# double-offset.net
KiCad netlist of a schematic drawn in EAGLE
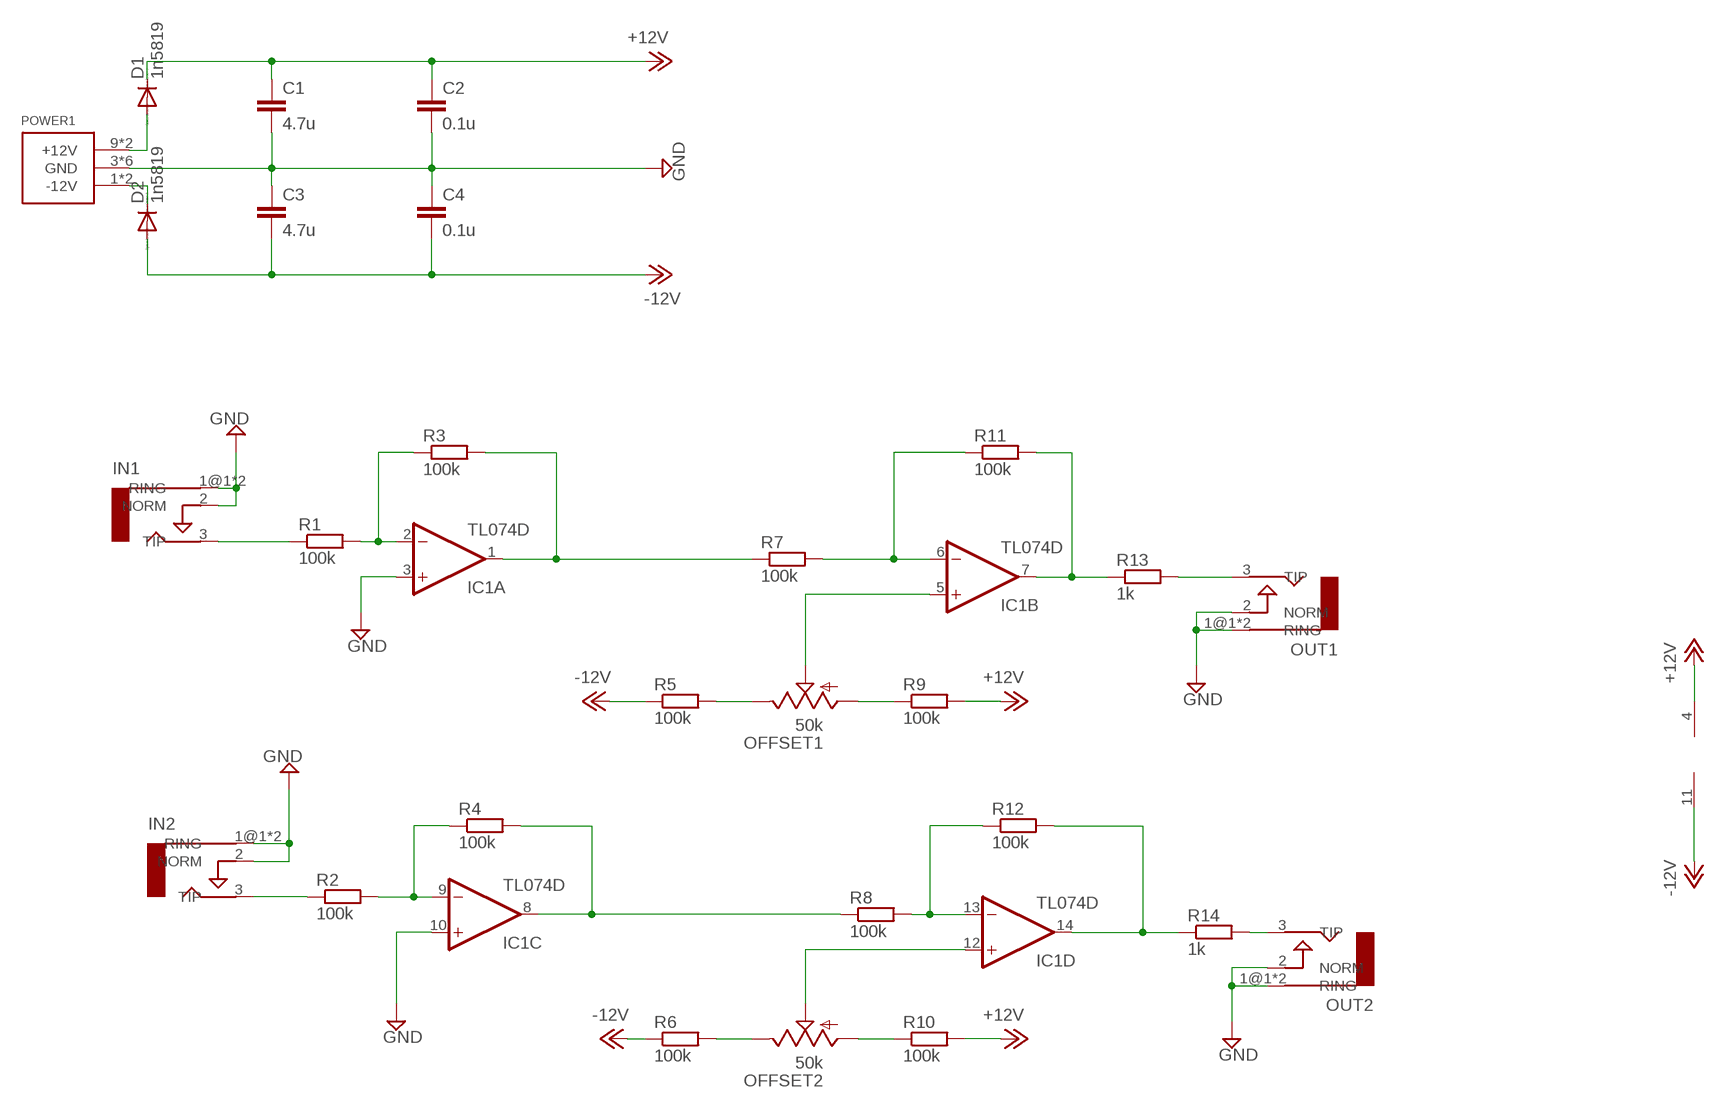
[diagram p0: schematic, sheet 1]

(export (version "E")
  (design (tool "Eeschema 10.0.6"))
  (components
    (comp (ref "C1")
      (value "4.7u")
      (footprint "eagle-import:C0805")
      (libsource (lib "eagle-import") (part "C-EUC0805"))
    )
    (comp (ref "C2")
      (value "0.1u")
      (footprint "eagle-import:C0805")
      (libsource (lib "eagle-import") (part "C-EUC0805"))
    )
    (comp (ref "C3")
      (value "4.7u")
      (footprint "eagle-import:C0805")
      (libsource (lib "eagle-import") (part "C-EUC0805"))
    )
    (comp (ref "C4")
      (value "0.1u")
      (footprint "eagle-import:C0805")
      (libsource (lib "eagle-import") (part "C-EUC0805"))
    )
    (comp (ref "D1")
      (value "1n5819")
      (footprint "eagle-import:SOD323-W")
      (libsource (lib "eagle-import") (part "DIODE-SOD323-W"))
    )
    (comp (ref "D2")
      (value "1n5819")
      (footprint "eagle-import:SOD323-W")
      (libsource (lib "eagle-import") (part "DIODE-SOD323-W"))
    )
    (comp (ref "IC1")
      (value "TL074D")
      (footprint "eagle-import:SO14")
      (libsource (lib "eagle-import") (part "TL074D"))
    )
    (comp (ref "IN1")
      (value "AUDIO-JACKERTHENVAR")
      (footprint "eagle-import:ERTHENVAR-JACK")
      (libsource (lib "eagle-import") (part "AUDIO-JACKERTHENVAR"))
    )
    (comp (ref "IN2")
      (value "AUDIO-JACKERTHENVAR")
      (footprint "eagle-import:ERTHENVAR-JACK")
      (libsource (lib "eagle-import") (part "AUDIO-JACKERTHENVAR"))
    )
    (comp (ref "OFFSET1")
      (value "50k")
      (footprint "eagle-import:9MM_SNAP-IN_POT")
      (libsource (lib "eagle-import") (part "9MM_SNAP-IN_POT_"))
    )
    (comp (ref "OFFSET2")
      (value "50k")
      (footprint "eagle-import:9MM_SNAP-IN_POT")
      (libsource (lib "eagle-import") (part "9MM_SNAP-IN_POT_"))
    )
    (comp (ref "OUT1")
      (value "AUDIO-JACKERTHENVAR")
      (footprint "eagle-import:ERTHENVAR-JACK")
      (libsource (lib "eagle-import") (part "AUDIO-JACKERTHENVAR"))
    )
    (comp (ref "OUT2")
      (value "AUDIO-JACKERTHENVAR")
      (footprint "eagle-import:ERTHENVAR-JACK")
      (libsource (lib "eagle-import") (part "AUDIO-JACKERTHENVAR"))
    )
    (comp (ref "POWER1")
      (value "POWER_SIMPLE10")
      (footprint "eagle-import:POWER_10")
      (libsource (lib "eagle-import") (part "POWER_SIMPLE10"))
    )
    (comp (ref "R1")
      (value "100k")
      (footprint "eagle-import:R0805")
      (libsource (lib "eagle-import") (part "R-EU_R0805"))
    )
    (comp (ref "R2")
      (value "100k")
      (footprint "eagle-import:R0805")
      (libsource (lib "eagle-import") (part "R-EU_R0805"))
    )
    (comp (ref "R3")
      (value "100k")
      (footprint "eagle-import:R0805")
      (libsource (lib "eagle-import") (part "R-EU_R0805"))
    )
    (comp (ref "R4")
      (value "100k")
      (footprint "eagle-import:R0805")
      (libsource (lib "eagle-import") (part "R-EU_R0805"))
    )
    (comp (ref "R5")
      (value "100k")
      (footprint "eagle-import:R0805")
      (libsource (lib "eagle-import") (part "R-EU_R0805"))
    )
    (comp (ref "R6")
      (value "100k")
      (footprint "eagle-import:R0805")
      (libsource (lib "eagle-import") (part "R-EU_R0805"))
    )
    (comp (ref "R7")
      (value "100k")
      (footprint "eagle-import:R0805")
      (libsource (lib "eagle-import") (part "R-EU_R0805"))
    )
    (comp (ref "R8")
      (value "100k")
      (footprint "eagle-import:R0805")
      (libsource (lib "eagle-import") (part "R-EU_R0805"))
    )
    (comp (ref "R9")
      (value "100k")
      (footprint "eagle-import:R0805")
      (libsource (lib "eagle-import") (part "R-EU_R0805"))
    )
    (comp (ref "R10")
      (value "100k")
      (footprint "eagle-import:R0805")
      (libsource (lib "eagle-import") (part "R-EU_R0805"))
    )
    (comp (ref "R11")
      (value "100k")
      (footprint "eagle-import:R0805")
      (libsource (lib "eagle-import") (part "R-EU_R0805"))
    )
    (comp (ref "R12")
      (value "100k")
      (footprint "eagle-import:R0805")
      (libsource (lib "eagle-import") (part "R-EU_R0805"))
    )
    (comp (ref "R13")
      (value "1k")
      (footprint "eagle-import:R0805")
      (libsource (lib "eagle-import") (part "R-EU_R0805"))
    )
    (comp (ref "R14")
      (value "1k")
      (footprint "eagle-import:R0805")
      (libsource (lib "eagle-import") (part "R-EU_R0805"))
    )
  )
  (nets
    (net (code "1") (name "+12V") (class "Default")
      (node (ref "C1") (pin "1") (pinfunction "1_1") (pintype "passive"))
      (node (ref "C2") (pin "1") (pinfunction "1_1") (pintype "passive"))
      (node (ref "D1") (pin "C") (pinfunction "C_C") (pintype "passive"))
      (node (ref "IC1") (pin "4") (pinfunction "V+_4") (pintype "power_in"))
      (node (ref "R10") (pin "2") (pinfunction "2_2") (pintype "passive"))
      (node (ref "R9") (pin "2") (pinfunction "2_2") (pintype "passive"))
    )
    (net (code "2") (name "-12V") (class "Default")
      (node (ref "C3") (pin "2") (pinfunction "2_2") (pintype "passive"))
      (node (ref "C4") (pin "2") (pinfunction "2_2") (pintype "passive"))
      (node (ref "D2") (pin "A") (pinfunction "A_A") (pintype "passive"))
      (node (ref "IC1") (pin "11") (pinfunction "V-_11") (pintype "power_in"))
      (node (ref "R5") (pin "1") (pinfunction "1_1") (pintype "passive"))
      (node (ref "R6") (pin "1") (pinfunction "1_1") (pintype "passive"))
    )
    (net (code "3") (name "GND") (class "Default")
      (node (ref "C1") (pin "2") (pinfunction "2_2") (pintype "passive"))
      (node (ref "C2") (pin "2") (pinfunction "2_2") (pintype "passive"))
      (node (ref "C3") (pin "1") (pinfunction "1_1") (pintype "passive"))
      (node (ref "C4") (pin "1") (pinfunction "1_1") (pintype "passive"))
      (node (ref "IC1") (pin "10") (pinfunction "+IN_10") (pintype "input"))
      (node (ref "IC1") (pin "3") (pinfunction "+IN_3") (pintype "input"))
      (node (ref "IN1") (pin "1@1") (pinfunction "RING_1@1") (pintype "bidirectional"))
      (node (ref "IN1") (pin "1@2") (pinfunction "RING_1@2") (pintype "bidirectional"))
      (node (ref "IN1") (pin "2") (pinfunction "NORM_2") (pintype "bidirectional"))
      (node (ref "IN2") (pin "1@1") (pinfunction "RING_1@1") (pintype "bidirectional"))
      (node (ref "IN2") (pin "1@2") (pinfunction "RING_1@2") (pintype "bidirectional"))
      (node (ref "IN2") (pin "2") (pinfunction "NORM_2") (pintype "bidirectional"))
      (node (ref "OUT1") (pin "1@1") (pinfunction "RING_1@1") (pintype "bidirectional"))
      (node (ref "OUT1") (pin "1@2") (pinfunction "RING_1@2") (pintype "bidirectional"))
      (node (ref "OUT1") (pin "2") (pinfunction "NORM_2") (pintype "bidirectional"))
      (node (ref "OUT2") (pin "1@1") (pinfunction "RING_1@1") (pintype "bidirectional"))
      (node (ref "OUT2") (pin "1@2") (pinfunction "RING_1@2") (pintype "bidirectional"))
      (node (ref "OUT2") (pin "2") (pinfunction "NORM_2") (pintype "bidirectional"))
      (node (ref "POWER1") (pin "3") (pinfunction "GND_3") (pintype "bidirectional"))
      (node (ref "POWER1") (pin "4") (pinfunction "GND_4") (pintype "bidirectional"))
      (node (ref "POWER1") (pin "5") (pinfunction "GND_5") (pintype "bidirectional"))
      (node (ref "POWER1") (pin "6") (pinfunction "GND_6") (pintype "bidirectional"))
      (node (ref "POWER1") (pin "7") (pinfunction "GND_7") (pintype "bidirectional"))
      (node (ref "POWER1") (pin "8") (pinfunction "GND_8") (pintype "bidirectional"))
    )
    (net (code "4") (name "Net-(D1-PadA)") (class "Default")
      (node (ref "D1") (pin "A") (pinfunction "A_A") (pintype "passive"))
      (node (ref "POWER1") (pin "10") (pinfunction "+12V_10") (pintype "bidirectional"))
      (node (ref "POWER1") (pin "9") (pinfunction "+12V_9") (pintype "bidirectional"))
    )
    (net (code "5") (name "Net-(D2-PadC)") (class "Default")
      (node (ref "D2") (pin "C") (pinfunction "C_C") (pintype "passive"))
      (node (ref "POWER1") (pin "1") (pinfunction "-12V_1") (pintype "bidirectional"))
      (node (ref "POWER1") (pin "2") (pinfunction "-12V_2") (pintype "bidirectional"))
    )
    (net (code "6") (name "Net-(IC1A--IN)") (class "Default")
      (node (ref "IC1") (pin "2") (pinfunction "-IN_2") (pintype "input"))
      (node (ref "R1") (pin "2") (pinfunction "2_2") (pintype "passive"))
      (node (ref "R3") (pin "1") (pinfunction "1_1") (pintype "passive"))
    )
    (net (code "7") (name "Net-(IC1A-OUT)") (class "Default")
      (node (ref "IC1") (pin "1") (pinfunction "OUT_1") (pintype "output"))
      (node (ref "R3") (pin "2") (pinfunction "2_2") (pintype "passive"))
      (node (ref "R7") (pin "1") (pinfunction "1_1") (pintype "passive"))
    )
    (net (code "8") (name "Net-(IC1B-+IN)") (class "Default")
      (node (ref "IC1") (pin "5") (pinfunction "+IN_5") (pintype "input"))
      (node (ref "OFFSET1") (pin "2") (pinfunction "S_2") (pintype "passive"))
    )
    (net (code "9") (name "Net-(IC1B--IN)") (class "Default")
      (node (ref "IC1") (pin "6") (pinfunction "-IN_6") (pintype "input"))
      (node (ref "R11") (pin "1") (pinfunction "1_1") (pintype "passive"))
      (node (ref "R7") (pin "2") (pinfunction "2_2") (pintype "passive"))
    )
    (net (code "10") (name "Net-(IC1B-OUT)") (class "Default")
      (node (ref "IC1") (pin "7") (pinfunction "OUT_7") (pintype "output"))
      (node (ref "R11") (pin "2") (pinfunction "2_2") (pintype "passive"))
      (node (ref "R13") (pin "1") (pinfunction "1_1") (pintype "passive"))
    )
    (net (code "11") (name "Net-(IC1C--IN)") (class "Default")
      (node (ref "IC1") (pin "9") (pinfunction "-IN_9") (pintype "input"))
      (node (ref "R2") (pin "2") (pinfunction "2_2") (pintype "passive"))
      (node (ref "R4") (pin "1") (pinfunction "1_1") (pintype "passive"))
    )
    (net (code "12") (name "Net-(IC1C-OUT)") (class "Default")
      (node (ref "IC1") (pin "8") (pinfunction "OUT_8") (pintype "output"))
      (node (ref "R4") (pin "2") (pinfunction "2_2") (pintype "passive"))
      (node (ref "R8") (pin "1") (pinfunction "1_1") (pintype "passive"))
    )
    (net (code "13") (name "Net-(IC1D-+IN)") (class "Default")
      (node (ref "IC1") (pin "12") (pinfunction "+IN_12") (pintype "input"))
      (node (ref "OFFSET2") (pin "2") (pinfunction "S_2") (pintype "passive"))
    )
    (net (code "14") (name "Net-(IC1D--IN)") (class "Default")
      (node (ref "IC1") (pin "13") (pinfunction "-IN_13") (pintype "input"))
      (node (ref "R12") (pin "1") (pinfunction "1_1") (pintype "passive"))
      (node (ref "R8") (pin "2") (pinfunction "2_2") (pintype "passive"))
    )
    (net (code "15") (name "Net-(IC1D-OUT)") (class "Default")
      (node (ref "IC1") (pin "14") (pinfunction "OUT_14") (pintype "output"))
      (node (ref "R12") (pin "2") (pinfunction "2_2") (pintype "passive"))
      (node (ref "R14") (pin "1") (pinfunction "1_1") (pintype "passive"))
    )
    (net (code "16") (name "Net-(IN1-TIP)") (class "Default")
      (node (ref "IN1") (pin "3") (pinfunction "TIP_3") (pintype "bidirectional"))
      (node (ref "R1") (pin "1") (pinfunction "1_1") (pintype "passive"))
    )
    (net (code "17") (name "Net-(IN2-TIP)") (class "Default")
      (node (ref "IN2") (pin "3") (pinfunction "TIP_3") (pintype "bidirectional"))
      (node (ref "R2") (pin "1") (pinfunction "1_1") (pintype "passive"))
    )
    (net (code "18") (name "Net-(OFFSET1-A)") (class "Default")
      (node (ref "OFFSET1") (pin "1") (pinfunction "A_1") (pintype "passive"))
      (node (ref "R9") (pin "1") (pinfunction "1_1") (pintype "passive"))
    )
    (net (code "19") (name "Net-(OFFSET1-E)") (class "Default")
      (node (ref "OFFSET1") (pin "3") (pinfunction "E_3") (pintype "passive"))
      (node (ref "R5") (pin "2") (pinfunction "2_2") (pintype "passive"))
    )
    (net (code "20") (name "Net-(OFFSET2-A)") (class "Default")
      (node (ref "OFFSET2") (pin "1") (pinfunction "A_1") (pintype "passive"))
      (node (ref "R10") (pin "1") (pinfunction "1_1") (pintype "passive"))
    )
    (net (code "21") (name "Net-(OFFSET2-E)") (class "Default")
      (node (ref "OFFSET2") (pin "3") (pinfunction "E_3") (pintype "passive"))
      (node (ref "R6") (pin "2") (pinfunction "2_2") (pintype "passive"))
    )
    (net (code "22") (name "Net-(OUT1-TIP)") (class "Default")
      (node (ref "OUT1") (pin "3") (pinfunction "TIP_3") (pintype "bidirectional"))
      (node (ref "R13") (pin "2") (pinfunction "2_2") (pintype "passive"))
    )
    (net (code "23") (name "Net-(OUT2-TIP)") (class "Default")
      (node (ref "OUT2") (pin "3") (pinfunction "TIP_3") (pintype "bidirectional"))
      (node (ref "R14") (pin "2") (pinfunction "2_2") (pintype "passive"))
    )
  )
)
